# INA250-Evaluation.net
KiCad netlist of a schematic drawn in EAGLE
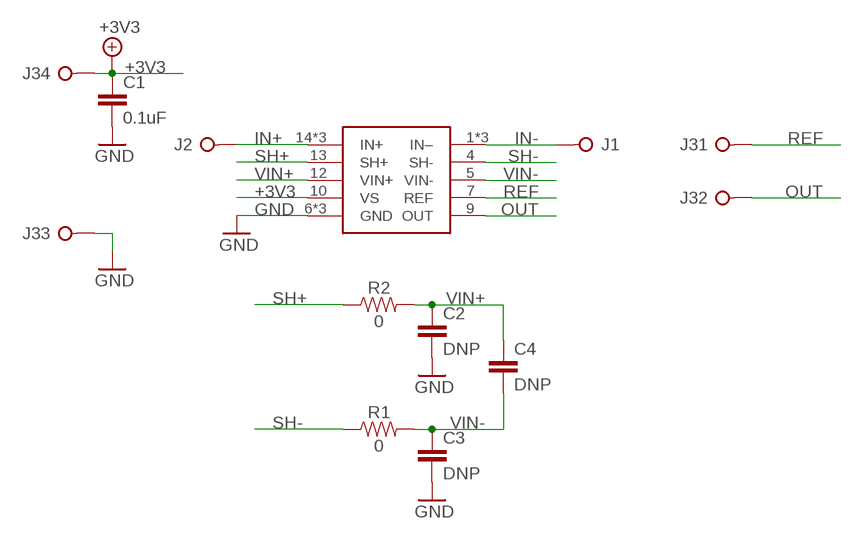
[diagram p0: schematic, sheet 1]

(export (version "E")
  (design (tool "Eeschema 10.0.6"))
  (components
    (comp (ref "C1")
      (value "0.1uF")
      (footprint "eagle-import:CAPACITOR-0805")
      (libsource (lib "eagle-import") (part "CAPACITOR-0805"))
    )
    (comp (ref "C2")
      (value "DNP")
      (footprint "eagle-import:CAPACITOR-0805")
      (libsource (lib "eagle-import") (part "CAPACITOR-0805"))
    )
    (comp (ref "C3")
      (value "DNP")
      (footprint "eagle-import:CAPACITOR-0805")
      (libsource (lib "eagle-import") (part "CAPACITOR-0805"))
    )
    (comp (ref "C4")
      (value "DNP")
      (footprint "eagle-import:CAPACITOR-0805")
      (libsource (lib "eagle-import") (part "CAPACITOR-0805"))
    )
    (comp (ref "IC1")
      (value "INA250")
      (footprint "eagle-import:TSSOP-16")
      (libsource (lib "eagle-import") (part "INA250"))
    )
    (comp (ref "J1")
      (value "PINHD-1X1BIG")
      (footprint "eagle-import:1X01-BIG")
      (libsource (lib "eagle-import") (part "PINHD-1X1BIG"))
    )
    (comp (ref "J2")
      (value "PINHD-1X1BIG")
      (footprint "eagle-import:1X01-BIG")
      (libsource (lib "eagle-import") (part "PINHD-1X1BIG"))
    )
    (comp (ref "J3")
      (value "PINHD-1X4")
      (footprint "eagle-import:1X04")
      (libsource (lib "eagle-import") (part "PINHD-1X4"))
    )
    (comp (ref "R1")
      (value "0")
      (footprint "eagle-import:RESISTOR-0805")
      (libsource (lib "eagle-import") (part "RESISTOR-0805"))
    )
    (comp (ref "R2")
      (value "0")
      (footprint "eagle-import:RESISTOR-0805")
      (libsource (lib "eagle-import") (part "RESISTOR-0805"))
    )
  )
  (nets
    (net (code "1") (name "+3V3") (class "Default")
      (node (ref "C1") (pin "1") (pinfunction "1_1") (pintype "passive"))
      (node (ref "IC1") (pin "10") (pinfunction "VS_10") (pintype "power_in"))
      (node (ref "J3") (pin "4") (pinfunction "KL_4") (pintype "passive"))
    )
    (net (code "2") (name "/IN+") (class "Default")
      (node (ref "IC1") (pin "14") (pinfunction "IN+_14") (pintype "passive"))
      (node (ref "IC1") (pin "15") (pinfunction "IN+_15") (pintype "passive"))
      (node (ref "IC1") (pin "16") (pinfunction "IN+_16") (pintype "passive"))
      (node (ref "J2") (pin "1") (pinfunction "KL_1") (pintype "passive"))
    )
    (net (code "3") (name "/IN-") (class "Default")
      (node (ref "IC1") (pin "1") (pinfunction "IN–_1") (pintype "passive"))
      (node (ref "IC1") (pin "2") (pinfunction "IN–_2") (pintype "passive"))
      (node (ref "IC1") (pin "3") (pinfunction "IN–_3") (pintype "passive"))
      (node (ref "J1") (pin "1") (pinfunction "KL_1") (pintype "passive"))
    )
    (net (code "4") (name "/OUT") (class "Default")
      (node (ref "IC1") (pin "9") (pinfunction "OUT_9") (pintype "output"))
      (node (ref "J3") (pin "2") (pinfunction "KL_2") (pintype "passive"))
    )
    (net (code "5") (name "/REF") (class "Default")
      (node (ref "IC1") (pin "7") (pinfunction "REF_7") (pintype "input"))
      (node (ref "J3") (pin "1") (pinfunction "KL_1") (pintype "passive"))
    )
    (net (code "6") (name "/SH+") (class "Default")
      (node (ref "IC1") (pin "13") (pinfunction "SH+_13") (pintype "output"))
      (node (ref "R2") (pin "1") (pinfunction "1_1") (pintype "passive"))
    )
    (net (code "7") (name "/SH-") (class "Default")
      (node (ref "IC1") (pin "4") (pinfunction "SH-_4") (pintype "output"))
      (node (ref "R1") (pin "1") (pinfunction "1_1") (pintype "passive"))
    )
    (net (code "8") (name "/VIN+") (class "Default")
      (node (ref "C2") (pin "1") (pinfunction "1_1") (pintype "passive"))
      (node (ref "C4") (pin "1") (pinfunction "1_1") (pintype "passive"))
      (node (ref "IC1") (pin "12") (pinfunction "VIN+_12") (pintype "input"))
      (node (ref "R2") (pin "2") (pinfunction "2_2") (pintype "passive"))
    )
    (net (code "9") (name "/VIN-") (class "Default")
      (node (ref "C3") (pin "1") (pinfunction "1_1") (pintype "passive"))
      (node (ref "C4") (pin "2") (pinfunction "2_2") (pintype "passive"))
      (node (ref "IC1") (pin "5") (pinfunction "VIN-_5") (pintype "input"))
      (node (ref "R1") (pin "2") (pinfunction "2_2") (pintype "passive"))
    )
    (net (code "10") (name "GND") (class "Default")
      (node (ref "C1") (pin "2") (pinfunction "2_2") (pintype "passive"))
      (node (ref "C2") (pin "2") (pinfunction "2_2") (pintype "passive"))
      (node (ref "C3") (pin "2") (pinfunction "2_2") (pintype "passive"))
      (node (ref "IC1") (pin "11") (pinfunction "GND_11") (pintype "power_in"))
      (node (ref "IC1") (pin "6") (pinfunction "GND_6") (pintype "power_in"))
      (node (ref "IC1") (pin "8") (pinfunction "GND_8") (pintype "power_in"))
      (node (ref "J3") (pin "3") (pinfunction "KL_3") (pintype "passive"))
    )
  )
)
